# Adafruit_MAX98357_Breakout.net
KiCad netlist of a schematic drawn in EAGLE
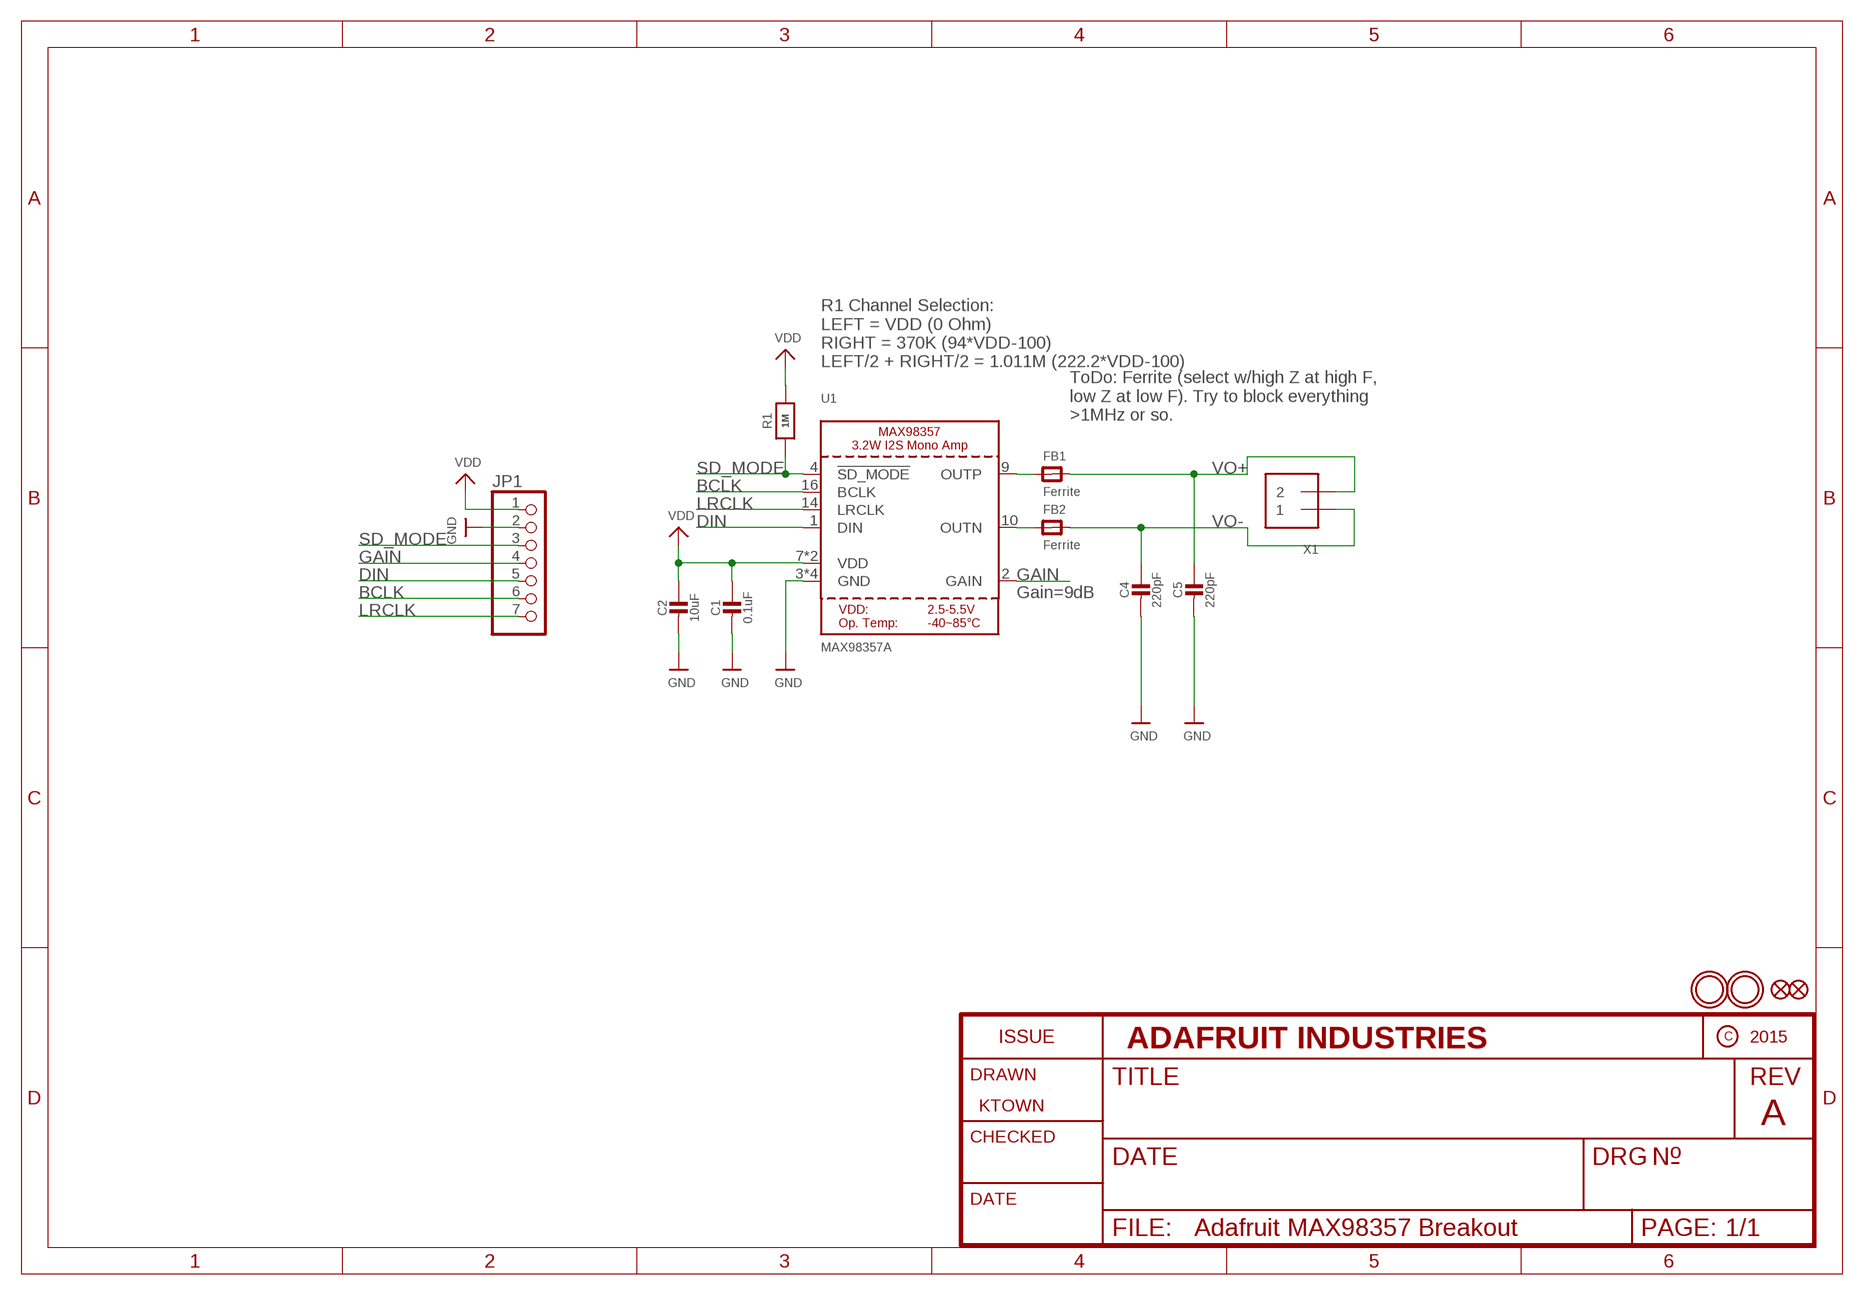
[diagram p0: schematic, sheet 1]

(export (version "E")
  (design (tool "Eeschema 10.0.6"))
  (components
    (comp (ref "C1")
      (value "0.1uF")
      (footprint "eagle-import:0805-NO")
      (libsource (lib "eagle-import") (part "CAP_CERAMIC0805-NOOUTLINE"))
    )
    (comp (ref "C2")
      (value "10uF")
      (footprint "eagle-import:0805-NO")
      (libsource (lib "eagle-import") (part "CAP_CERAMIC0805-NOOUTLINE"))
    )
    (comp (ref "C4")
      (value "220pF")
      (footprint "eagle-import:0805-NO")
      (libsource (lib "eagle-import") (part "CAP_CERAMIC0805-NOOUTLINE"))
    )
    (comp (ref "C5")
      (value "220pF")
      (footprint "eagle-import:0805-NO")
      (libsource (lib "eagle-import") (part "CAP_CERAMIC0805-NOOUTLINE"))
    )
    (comp (ref "FB1")
      (value "Ferrite")
      (footprint "eagle-import:0805-NO")
      (libsource (lib "eagle-import") (part "FERRITE-0805NO"))
    )
    (comp (ref "FB2")
      (value "Ferrite")
      (footprint "eagle-import:0805-NO")
      (libsource (lib "eagle-import") (part "FERRITE-0805NO"))
    )
    (comp (ref "FID1")
      (value "FIDUCIAL\"\"")
      (footprint "eagle-import:FIDUCIAL_1MM")
      (libsource (lib "eagle-import") (part "FIDUCIAL{dblquote}{dblquote}"))
    )
    (comp (ref "FID2")
      (value "FIDUCIAL\"\"")
      (footprint "eagle-import:FIDUCIAL_1MM")
      (libsource (lib "eagle-import") (part "FIDUCIAL{dblquote}{dblquote}"))
    )
    (comp (ref "JP1")
      (value "HEADER-1X7THICKER")
      (footprint "eagle-import:1X07_ROUND_76")
      (libsource (lib "eagle-import") (part "HEADER-1X7THICKER"))
    )
    (comp (ref "R1")
      (value "1M")
      (footprint "eagle-import:0805-NO")
      (libsource (lib "eagle-import") (part "RESISTOR0805_NOOUTLINE"))
    )
    (comp (ref "U$9")
      (value "MOUNTINGHOLE2.5")
      (footprint "eagle-import:MOUNTINGHOLE_2.5_PLATED")
      (libsource (lib "eagle-import") (part "MOUNTINGHOLE2.5"))
    )
    (comp (ref "U$10")
      (value "MOUNTINGHOLE2.5")
      (footprint "eagle-import:MOUNTINGHOLE_2.5_PLATED")
      (libsource (lib "eagle-import") (part "MOUNTINGHOLE2.5"))
    )
    (comp (ref "U1")
      (value "MAX98357A")
      (footprint "eagle-import:QFN16_3MM")
      (libsource (lib "eagle-import") (part "AUDIOAMP_MAX98357"))
    )
    (comp (ref "X1")
      (value "TERMBLOCK_1X2")
      (footprint "eagle-import:TERMBLOCK_1X2-3.5MM")
      (libsource (lib "eagle-import") (part "TERMBLOCK_1X2"))
    )
  )
  (nets
    (net (code "1") (name "/BCLK") (class "Default")
      (node (ref "JP1") (pin "6") (pinfunction "6_6") (pintype "passive"))
      (node (ref "U1") (pin "16") (pinfunction "BCLK_16") (pintype "bidirectional"))
    )
    (net (code "2") (name "/DIN") (class "Default")
      (node (ref "JP1") (pin "5") (pinfunction "5_5") (pintype "passive"))
      (node (ref "U1") (pin "1") (pinfunction "DIN_1") (pintype "bidirectional"))
    )
    (net (code "3") (name "/GAIN") (class "Default")
      (node (ref "JP1") (pin "4") (pinfunction "4_4") (pintype "passive"))
      (node (ref "U1") (pin "2") (pinfunction "GAIN_2") (pintype "bidirectional"))
    )
    (net (code "4") (name "/LRCLK") (class "Default")
      (node (ref "JP1") (pin "7") (pinfunction "7_7") (pintype "passive"))
      (node (ref "U1") (pin "14") (pinfunction "LRCLK_14") (pintype "bidirectional"))
    )
    (net (code "5") (name "/SD_MODE") (class "Default")
      (node (ref "JP1") (pin "3") (pinfunction "3_3") (pintype "passive"))
      (node (ref "R1") (pin "1") (pinfunction "1_1") (pintype "passive"))
      (node (ref "U1") (pin "4") (pinfunction "~{SD_MODE}_4") (pintype "bidirectional"))
    )
    (net (code "6") (name "/VO+") (class "Default")
      (node (ref "C5") (pin "1") (pinfunction "1_1") (pintype "passive"))
      (node (ref "FB1") (pin "2") (pinfunction "P$2_2") (pintype "passive"))
      (node (ref "X1") (pin "2") (pinfunction "2_2") (pintype "passive"))
    )
    (net (code "7") (name "/VO-") (class "Default")
      (node (ref "C4") (pin "1") (pinfunction "1_1") (pintype "passive"))
      (node (ref "FB2") (pin "2") (pinfunction "P$2_2") (pintype "passive"))
      (node (ref "X1") (pin "1") (pinfunction "1_1") (pintype "passive"))
    )
    (net (code "8") (name "GND") (class "Default")
      (node (ref "C1") (pin "2") (pinfunction "2_2") (pintype "passive"))
      (node (ref "C2") (pin "2") (pinfunction "2_2") (pintype "passive"))
      (node (ref "C4") (pin "2") (pinfunction "2_2") (pintype "passive"))
      (node (ref "C5") (pin "2") (pinfunction "2_2") (pintype "passive"))
      (node (ref "JP1") (pin "2") (pinfunction "2_2") (pintype "passive"))
      (node (ref "U1") (pin "11") (pinfunction "GND_11") (pintype "power_in"))
      (node (ref "U1") (pin "15") (pinfunction "GND_15") (pintype "power_in"))
      (node (ref "U1") (pin "3") (pinfunction "GND_3") (pintype "power_in"))
      (node (ref "U1") (pin "THERMAL") (pinfunction "GND_THERMAL") (pintype "power_in"))
    )
    (net (code "9") (name "Net-(FB1-P$1)") (class "Default")
      (node (ref "FB1") (pin "1") (pinfunction "P$1_1") (pintype "passive"))
      (node (ref "U1") (pin "9") (pinfunction "OUTP_9") (pintype "output"))
    )
    (net (code "10") (name "Net-(FB2-P$1)") (class "Default")
      (node (ref "FB2") (pin "1") (pinfunction "P$1_1") (pintype "passive"))
      (node (ref "U1") (pin "10") (pinfunction "OUTN_10") (pintype "output"))
    )
    (net (code "11") (name "VDD") (class "Default")
      (node (ref "C1") (pin "1") (pinfunction "1_1") (pintype "passive"))
      (node (ref "C2") (pin "1") (pinfunction "1_1") (pintype "passive"))
      (node (ref "JP1") (pin "1") (pinfunction "1_1") (pintype "passive"))
      (node (ref "R1") (pin "2") (pinfunction "2_2") (pintype "passive"))
      (node (ref "U1") (pin "7") (pinfunction "VDD_7") (pintype "power_in"))
      (node (ref "U1") (pin "8") (pinfunction "VDD_8") (pintype "power_in"))
    )
  )
)
